# SCH_Guava_PCB.net
KiCad netlist of a schematic drawn in EasyEDA
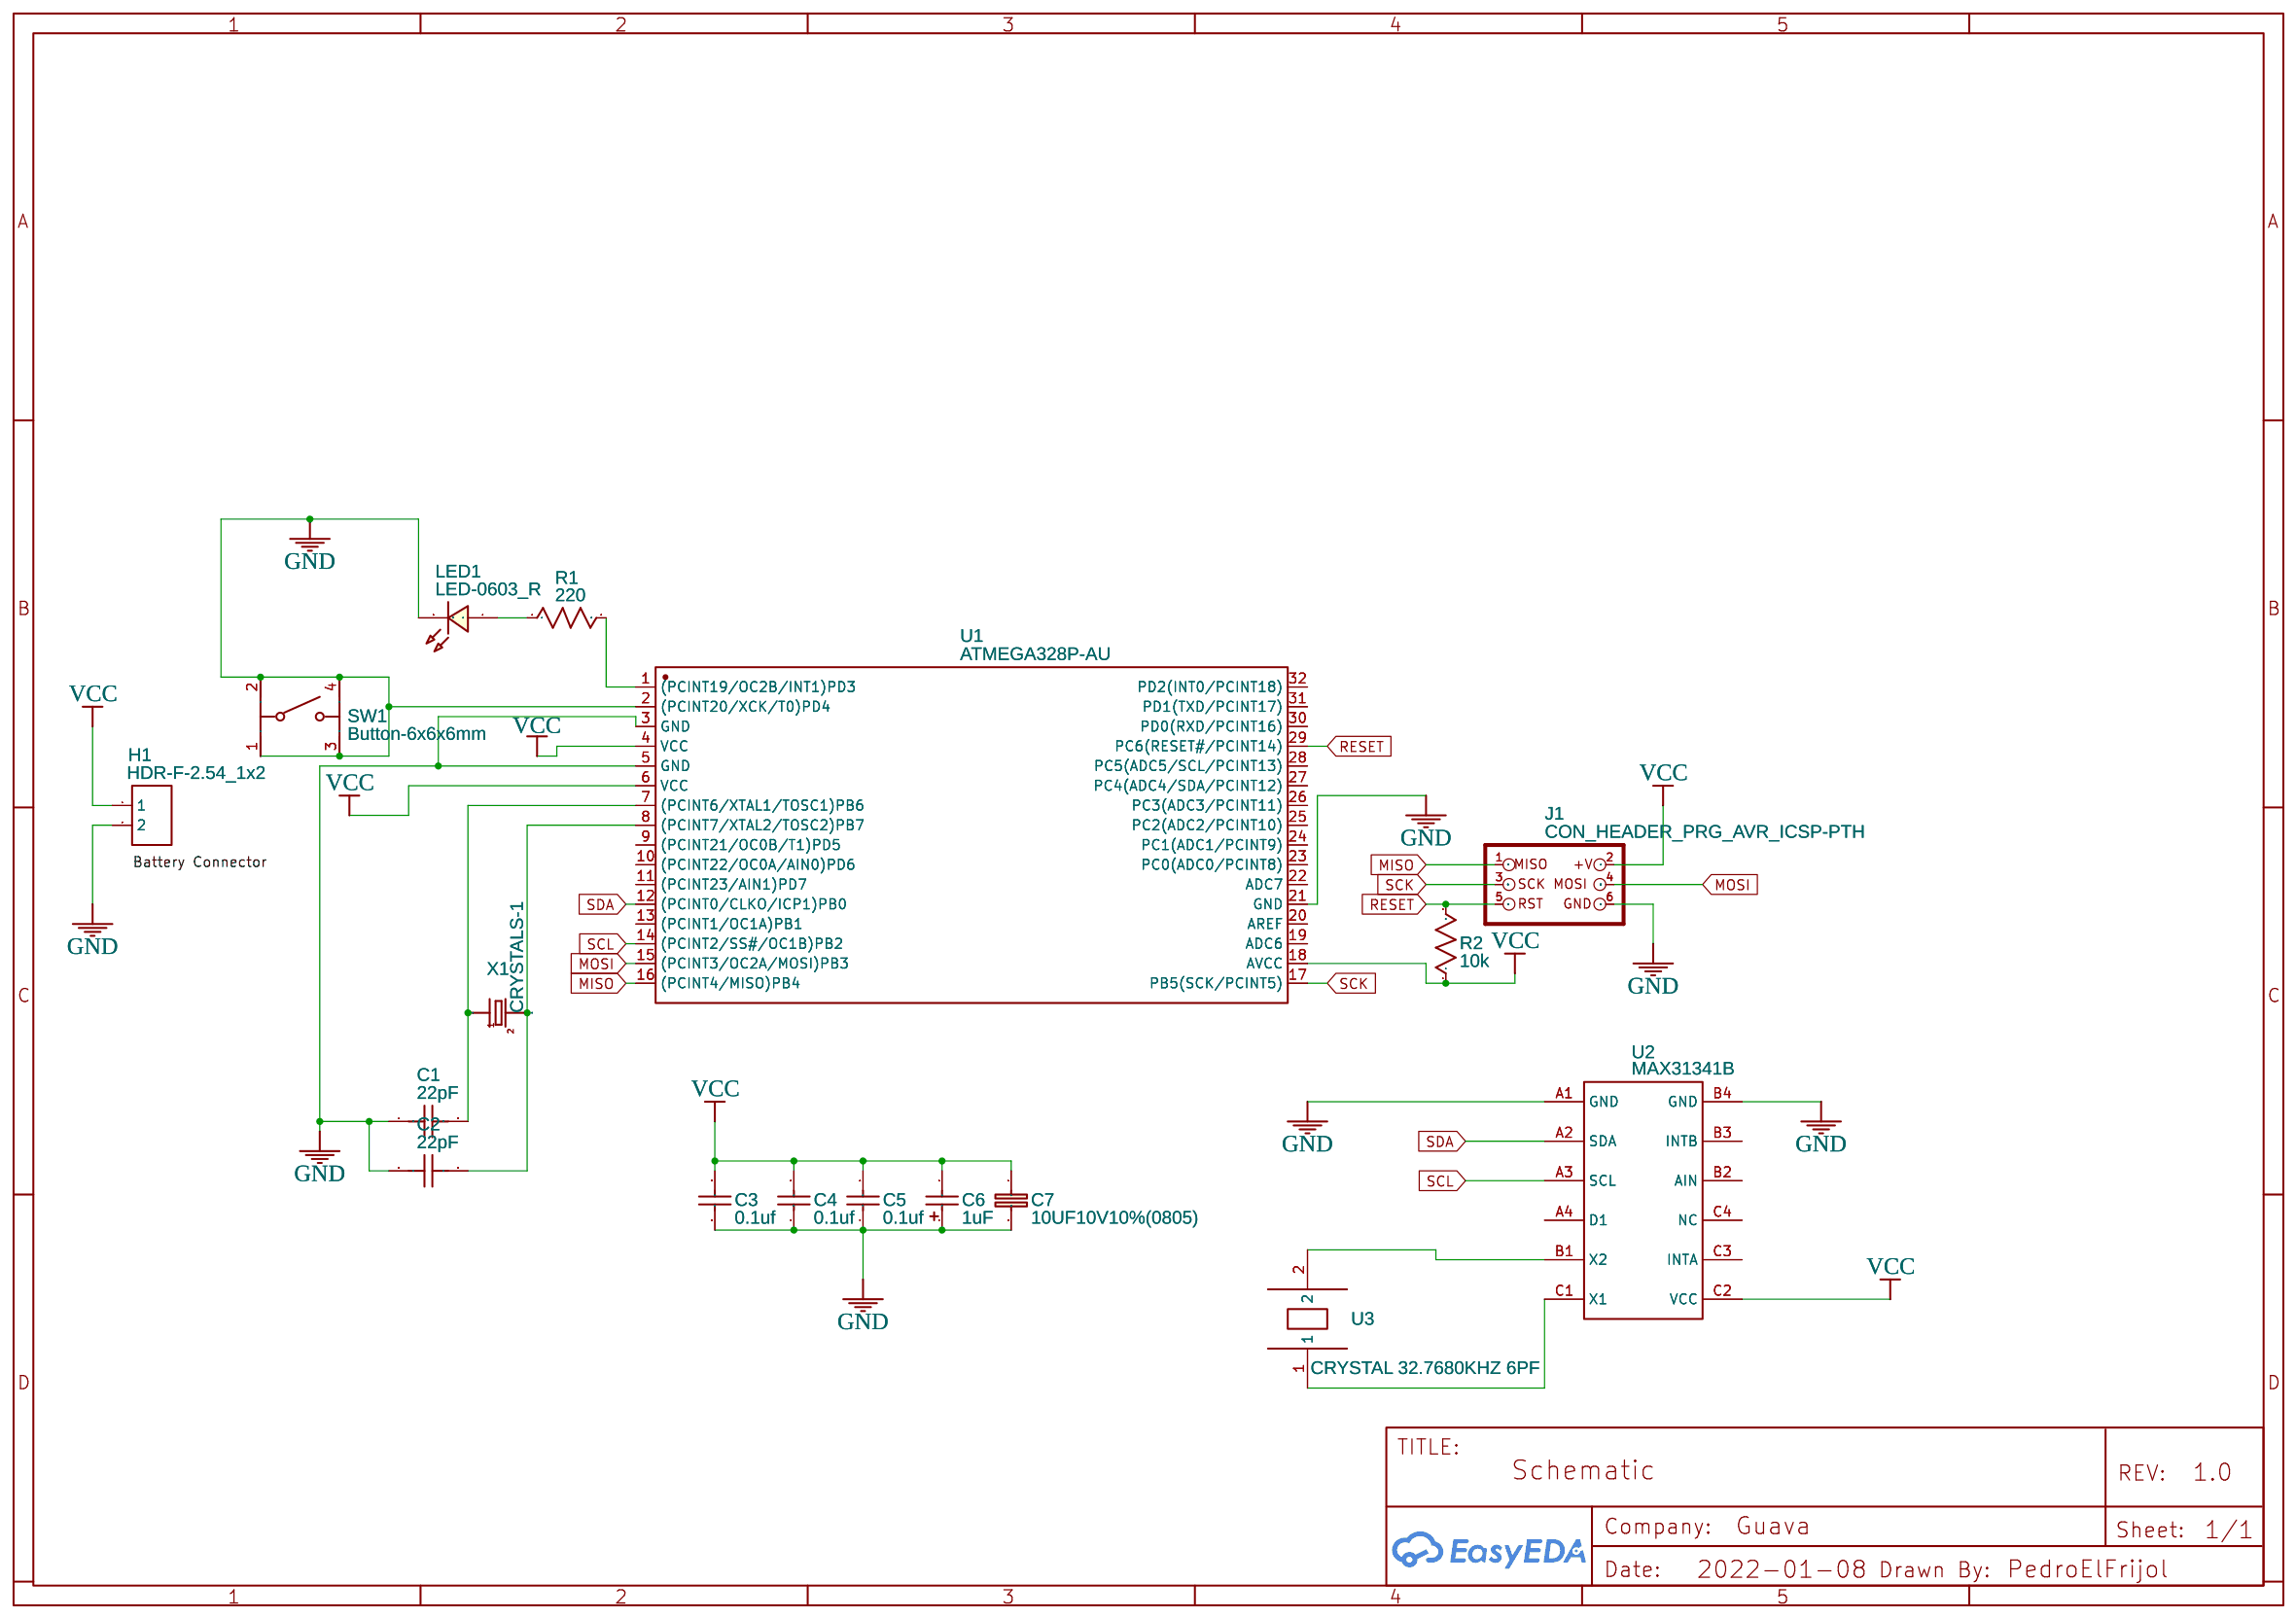
[diagram p0: schematic sheet]

(export (version "E")
  (design (tool "Eeschema 10.0.6"))
  (components
    (comp (ref "C1") (value "22pF") (libsource (lib "") (part "C_0603_US")))
    (comp (ref "C2") (value "22pF") (libsource (lib "") (part "C_0603_US")))
    (comp (ref "C3")
      (value "0.1uf")
      (fields
        (field (name "BOM_Manufacturer Part") "CT4-0805Y104M500")
        (field (name "BOM_Supplier Part") "undefined")
      )
      (libsource (lib "") (part "0.1uf"))
    )
    (comp (ref "C4")
      (value "0.1uf")
      (fields
        (field (name "BOM_Manufacturer Part") "CT4-0805Y104M500")
        (field (name "BOM_Supplier Part") "undefined")
      )
      (libsource (lib "") (part "0.1uf"))
    )
    (comp (ref "C5")
      (value "0.1uf")
      (fields
        (field (name "BOM_Manufacturer Part") "CT4-0805Y104M500")
        (field (name "BOM_Supplier Part") "undefined")
      )
      (libsource (lib "") (part "0.1uf"))
    )
    (comp (ref "C6")
      (value "1uF")
      (fields
        (field (name "BOM_Manufacturer Part") "TAP105K050SCS")
        (field (name "BOM_Supplier Part") "C52309")
      )
      (libsource (lib "") (part "1uF"))
    )
    (comp (ref "C7") (value "10UF10V10%(0805)") (libsource (lib "") (part "10UF10V10%(0805)")))
    (comp (ref "H1")
      (value "HDR-F-2.54_1x2")
      (fields (field (name "BOM_Supplier Part") "C49661"))
      (libsource (lib "") (part "HDR-F-2.54_1x2"))
    )
    (comp (ref "J1")
      (value "CON_HEADER_PRG_AVR_ICSP-PTH")
      (libsource (lib "") (part "CON_HEADER_PRG_AVR_ICSP-PTH"))
    )
    (comp (ref "LED1")
      (value "LED-0603_R")
      (fields
        (field (name "BOM_Manufacturer Part") "19-217/R6C-AL1M2VY/3T")
        (field (name "BOM_Supplier Part") "C72044")
      )
      (libsource (lib "") (part "LED-0603_R"))
    )
    (comp (ref "R1") (value "220") (libsource (lib "") (part "R_0603_US_1")))
    (comp (ref "R2") (value "10k") (libsource (lib "") (part "R_0603_US")))
    (comp (ref "SW1")
      (value "Button-6x6x6mm")
      (fields
        (field (name "BOM_Manufacturer Part") "Switch,6*6*6Plastic head,260G, 0.25mm,Straight line")
        (field (name "BOM_Supplier Part") "C71836")
      )
      (libsource (lib "") (part "Button-6x6x6mm"))
    )
    (comp (ref "U1")
      (value "ATMEGA328P-AU")
      (fields (field (name "BOM_Supplier Part") "C14877"))
      (libsource (lib "") (part "ATMEGA328P-AU"))
    )
    (comp (ref "U2")
      (value "MAX31341B")
      (fields
        (field (name "BOM_Manufacturer Part") "MAX31341BEWC+")
        (field (name "BOM_Supplier Part") "MAX31341BEWC+-ND")
      )
      (libsource (lib "") (part "MAX31341B"))
    )
    (comp (ref "U3")
      (value "CRYSTAL 32.7680KHZ 6PF")
      (fields
        (field (name "BOM_Manufacturer Part") "CFS-20632768DZBB")
        (field (name "BOM_Supplier Part") "300-8301-ND")
      )
      (libsource (lib "") (part "CRYSTAL 32.7680KHZ 6PF T/H"))
    )
    (comp (ref "X1") (value "CRYSTALS-1") (libsource (lib "") (part "CRYSTALS-1")))
  )
  (nets
    (net (code "2") (name "GND") (class "Default")
      (node (ref "C1") (pin "1") (pinfunction "1_1") (pintype "unspecified"))
      (node (ref "C2") (pin "1") (pinfunction "1_1") (pintype "unspecified"))
      (node (ref "C3") (pin "1") (pinfunction "1_1") (pintype "input"))
      (node (ref "C4") (pin "1") (pinfunction "1_1") (pintype "input"))
      (node (ref "C5") (pin "1") (pinfunction "1_1") (pintype "input"))
      (node (ref "C6") (pin "1") (pinfunction "1_1") (pintype "input"))
      (node (ref "C7") (pin "2") (pinfunction "2_2") (pintype "unspecified"))
      (node (ref "H1") (pin "2") (pinfunction "2_2") (pintype "input"))
      (node (ref "J1") (pin "6") (pinfunction "GND_6") (pintype "unspecified"))
      (node (ref "LED1") (pin "2") (pinfunction "2_2") (pintype "unspecified"))
      (node (ref "SW1") (pin "1") (pinfunction "1_1") (pintype "unspecified"))
      (node (ref "SW1") (pin "2") (pinfunction "2_2") (pintype "unspecified"))
      (node (ref "SW1") (pin "3") (pinfunction "3_3") (pintype "unspecified"))
      (node (ref "SW1") (pin "4") (pinfunction "4_4") (pintype "unspecified"))
      (node (ref "U1") (pin "2") (pinfunction "(PCINT20/XCK/T0)PD4_2") (pintype "unspecified"))
      (node (ref "U1") (pin "21") (pinfunction "GND_21") (pintype "unspecified"))
      (node (ref "U1") (pin "3") (pinfunction "GND_3") (pintype "unspecified"))
      (node (ref "U1") (pin "5") (pinfunction "GND_5") (pintype "unspecified"))
      (node (ref "U2") (pin "A1") (pinfunction "GND_A1") (pintype "unspecified"))
      (node (ref "U2") (pin "B4") (pinfunction "GND_B4") (pintype "unspecified"))
    )
    (net (code "3") (name "MISO") (class "Default")
      (node (ref "J1") (pin "1") (pinfunction "MISO_1") (pintype "unspecified"))
      (node (ref "U1") (pin "16") (pinfunction "(PCINT4/MISO)PB4_16") (pintype "unspecified"))
    )
    (net (code "4") (name "MOSI") (class "Default")
      (node (ref "J1") (pin "4") (pinfunction "MOSI_4") (pintype "unspecified"))
      (node (ref "U1") (pin "15") (pinfunction "(PCINT3/OC2A/MOSI)PB3_15") (pintype "unspecified"))
    )
    (net (code "5") (name "Net-(LED1-Pad1)") (class "Default")
      (node (ref "LED1") (pin "1") (pinfunction "1_1") (pintype "unspecified"))
      (node (ref "R1") (pin "1") (pinfunction "1_1") (pintype "unspecified"))
    )
    (net (code "6") (name "Net-(U1-(PCINT6{slash}XTAL1{slash}TOSC1)PB6)") (class "Default")
      (node (ref "C1") (pin "2") (pinfunction "2_2") (pintype "unspecified"))
      (node (ref "U1") (pin "7") (pinfunction "(PCINT6/XTAL1/TOSC1)PB6_7") (pintype "unspecified"))
      (node (ref "X1") (pin "1") (pinfunction "1_1") (pintype "unspecified"))
    )
    (net (code "7") (name "Net-(U1-(PCINT7{slash}XTAL2{slash}TOSC2)PB7)") (class "Default")
      (node (ref "C2") (pin "2") (pinfunction "2_2") (pintype "unspecified"))
      (node (ref "U1") (pin "8") (pinfunction "(PCINT7/XTAL2/TOSC2)PB7_8") (pintype "unspecified"))
      (node (ref "X1") (pin "2") (pinfunction "2_2") (pintype "unspecified"))
    )
    (net (code "8") (name "Net-(U1-(PCINT19{slash}OC2B{slash}INT1)PD3)") (class "Default")
      (node (ref "R1") (pin "2") (pinfunction "2_2") (pintype "unspecified"))
      (node (ref "U1") (pin "1") (pinfunction "(PCINT19/OC2B/INT1)PD3_1") (pintype "unspecified"))
    )
    (net (code "9") (name "Net-(U2-X1)") (class "Default")
      (node (ref "U2") (pin "C1") (pinfunction "X1_C1") (pintype "unspecified"))
      (node (ref "U3") (pin "1") (pinfunction "1_1") (pintype "unspecified"))
    )
    (net (code "10") (name "Net-(U2-X2)") (class "Default")
      (node (ref "U2") (pin "B1") (pinfunction "X2_B1") (pintype "unspecified"))
      (node (ref "U3") (pin "2") (pinfunction "2_2") (pintype "unspecified"))
    )
    (net (code "11") (name "RESET") (class "Default")
      (node (ref "J1") (pin "5") (pinfunction "RST_5") (pintype "unspecified"))
      (node (ref "R2") (pin "2") (pinfunction "2_2") (pintype "unspecified"))
      (node (ref "U1") (pin "29") (pinfunction "PC6(RESET#/PCINT14)_29") (pintype "unspecified"))
    )
    (net (code "12") (name "SCK") (class "Default")
      (node (ref "J1") (pin "3") (pinfunction "SCK_3") (pintype "unspecified"))
      (node (ref "U1") (pin "17") (pinfunction "PB5(SCK/PCINT5)_17") (pintype "unspecified"))
    )
    (net (code "13") (name "SCL") (class "Default")
      (node (ref "U1") (pin "14") (pinfunction "(PCINT2/SS#/OC1B)PB2_14") (pintype "unspecified"))
      (node (ref "U2") (pin "A3") (pinfunction "SCL_A3") (pintype "unspecified"))
    )
    (net (code "14") (name "SDA") (class "Default")
      (node (ref "U1") (pin "12") (pinfunction "(PCINT0/CLKO/ICP1)PB0_12") (pintype "unspecified"))
      (node (ref "U2") (pin "A2") (pinfunction "SDA_A2") (pintype "unspecified"))
    )
    (net (code "15") (name "VCC") (class "Default")
      (node (ref "C3") (pin "2") (pinfunction "2_2") (pintype "input"))
      (node (ref "C4") (pin "2") (pinfunction "2_2") (pintype "input"))
      (node (ref "C5") (pin "2") (pinfunction "2_2") (pintype "input"))
      (node (ref "C6") (pin "2") (pinfunction "2_2") (pintype "input"))
      (node (ref "C7") (pin "1") (pinfunction "1_1") (pintype "unspecified"))
      (node (ref "H1") (pin "1") (pinfunction "1_1") (pintype "input"))
      (node (ref "J1") (pin "2") (pinfunction "+V_2") (pintype "unspecified"))
      (node (ref "R2") (pin "1") (pinfunction "1_1") (pintype "unspecified"))
      (node (ref "U1") (pin "18") (pinfunction "AVCC_18") (pintype "unspecified"))
      (node (ref "U1") (pin "4") (pinfunction "VCC_4") (pintype "unspecified"))
      (node (ref "U1") (pin "6") (pinfunction "VCC_6") (pintype "unspecified"))
      (node (ref "U2") (pin "C2") (pinfunction "VCC_C2") (pintype "unspecified"))
    )
    (net (code "16") (name "unconnected-(U1-(PCINT1{slash}OC1A)PB1-Pad13)") (class "Default")
      (node (ref "U1") (pin "13") (pinfunction "(PCINT1/OC1A)PB1_13") (pintype "unspecified"))
    )
    (net (code "17") (name "unconnected-(U1-(PCINT21{slash}OC0B{slash}T1)PD5-Pad9)") (class "Default")
      (node (ref "U1") (pin "9") (pinfunction "(PCINT21/OC0B/T1)PD5_9") (pintype "unspecified"))
    )
    (net (code "18") (name "unconnected-(U1-(PCINT22{slash}OC0A{slash}AIN0)PD6-Pad10)") (class "Default")
      (node (ref "U1") (pin "10") (pinfunction "(PCINT22/OC0A/AIN0)PD6_10") (pintype "unspecified"))
    )
    (net (code "19") (name "unconnected-(U1-(PCINT23{slash}AIN1)PD7-Pad11)") (class "Default")
      (node (ref "U1") (pin "11") (pinfunction "(PCINT23/AIN1)PD7_11") (pintype "unspecified"))
    )
    (net (code "20") (name "unconnected-(U1-ADC6-Pad19)") (class "Default")
      (node (ref "U1") (pin "19") (pinfunction "ADC6_19") (pintype "unspecified"))
    )
    (net (code "21") (name "unconnected-(U1-ADC7-Pad22)") (class "Default")
      (node (ref "U1") (pin "22") (pinfunction "ADC7_22") (pintype "unspecified"))
    )
    (net (code "22") (name "unconnected-(U1-AREF-Pad20)") (class "Default")
      (node (ref "U1") (pin "20") (pinfunction "AREF_20") (pintype "unspecified"))
    )
    (net (code "23") (name "unconnected-(U1-PC0(ADC0{slash}PCINT8)-Pad23)") (class "Default")
      (node (ref "U1") (pin "23") (pinfunction "PC0(ADC0/PCINT8)_23") (pintype "unspecified"))
    )
    (net (code "24") (name "unconnected-(U1-PC1(ADC1{slash}PCINT9)-Pad24)") (class "Default")
      (node (ref "U1") (pin "24") (pinfunction "PC1(ADC1/PCINT9)_24") (pintype "unspecified"))
    )
    (net (code "25") (name "unconnected-(U1-PC2(ADC2{slash}PCINT10)-Pad25)") (class "Default")
      (node (ref "U1") (pin "25") (pinfunction "PC2(ADC2/PCINT10)_25") (pintype "unspecified"))
    )
    (net (code "26") (name "unconnected-(U1-PC3(ADC3{slash}PCINT11)-Pad26)") (class "Default")
      (node (ref "U1") (pin "26") (pinfunction "PC3(ADC3/PCINT11)_26") (pintype "unspecified"))
    )
    (net (code "27") (name "unconnected-(U1-PC4(ADC4{slash}SDA{slash}PCINT12)-Pad27)") (class "Default")
      (node (ref "U1") (pin "27") (pinfunction "PC4(ADC4/SDA/PCINT12)_27") (pintype "unspecified"))
    )
    (net (code "28") (name "unconnected-(U1-PC5(ADC5{slash}SCL{slash}PCINT13)-Pad28)") (class "Default")
      (node (ref "U1") (pin "28") (pinfunction "PC5(ADC5/SCL/PCINT13)_28") (pintype "unspecified"))
    )
    (net (code "29") (name "unconnected-(U1-PD0(RXD{slash}PCINT16)-Pad30)") (class "Default")
      (node (ref "U1") (pin "30") (pinfunction "PD0(RXD/PCINT16)_30") (pintype "unspecified"))
    )
    (net (code "30") (name "unconnected-(U1-PD1(TXD{slash}PCINT17)-Pad31)") (class "Default")
      (node (ref "U1") (pin "31") (pinfunction "PD1(TXD/PCINT17)_31") (pintype "unspecified"))
    )
    (net (code "31") (name "unconnected-(U1-PD2(INT0{slash}PCINT18)-Pad32)") (class "Default")
      (node (ref "U1") (pin "32") (pinfunction "PD2(INT0/PCINT18)_32") (pintype "unspecified"))
    )
    (net (code "32") (name "unconnected-(U2-AIN-PadB2)") (class "Default")
      (node (ref "U2") (pin "B2") (pinfunction "AIN_B2") (pintype "unspecified"))
    )
    (net (code "33") (name "unconnected-(U2-D1-PadA4)") (class "Default")
      (node (ref "U2") (pin "A4") (pinfunction "D1_A4") (pintype "unspecified"))
    )
    (net (code "34") (name "unconnected-(U2-INTA-PadC3)") (class "Default")
      (node (ref "U2") (pin "C3") (pinfunction "INTA_C3") (pintype "unspecified"))
    )
    (net (code "35") (name "unconnected-(U2-INTB-PadB3)") (class "Default")
      (node (ref "U2") (pin "B3") (pinfunction "INTB_B3") (pintype "unspecified"))
    )
    (net (code "36") (name "unconnected-(U2-NC-PadC4)") (class "Default")
      (node (ref "U2") (pin "C4") (pinfunction "NC_C4") (pintype "unspecified"))
    )
  )
)
